# target_USB_interfaces_v3.net
KiCad netlist of a schematic drawn in Altium Designer
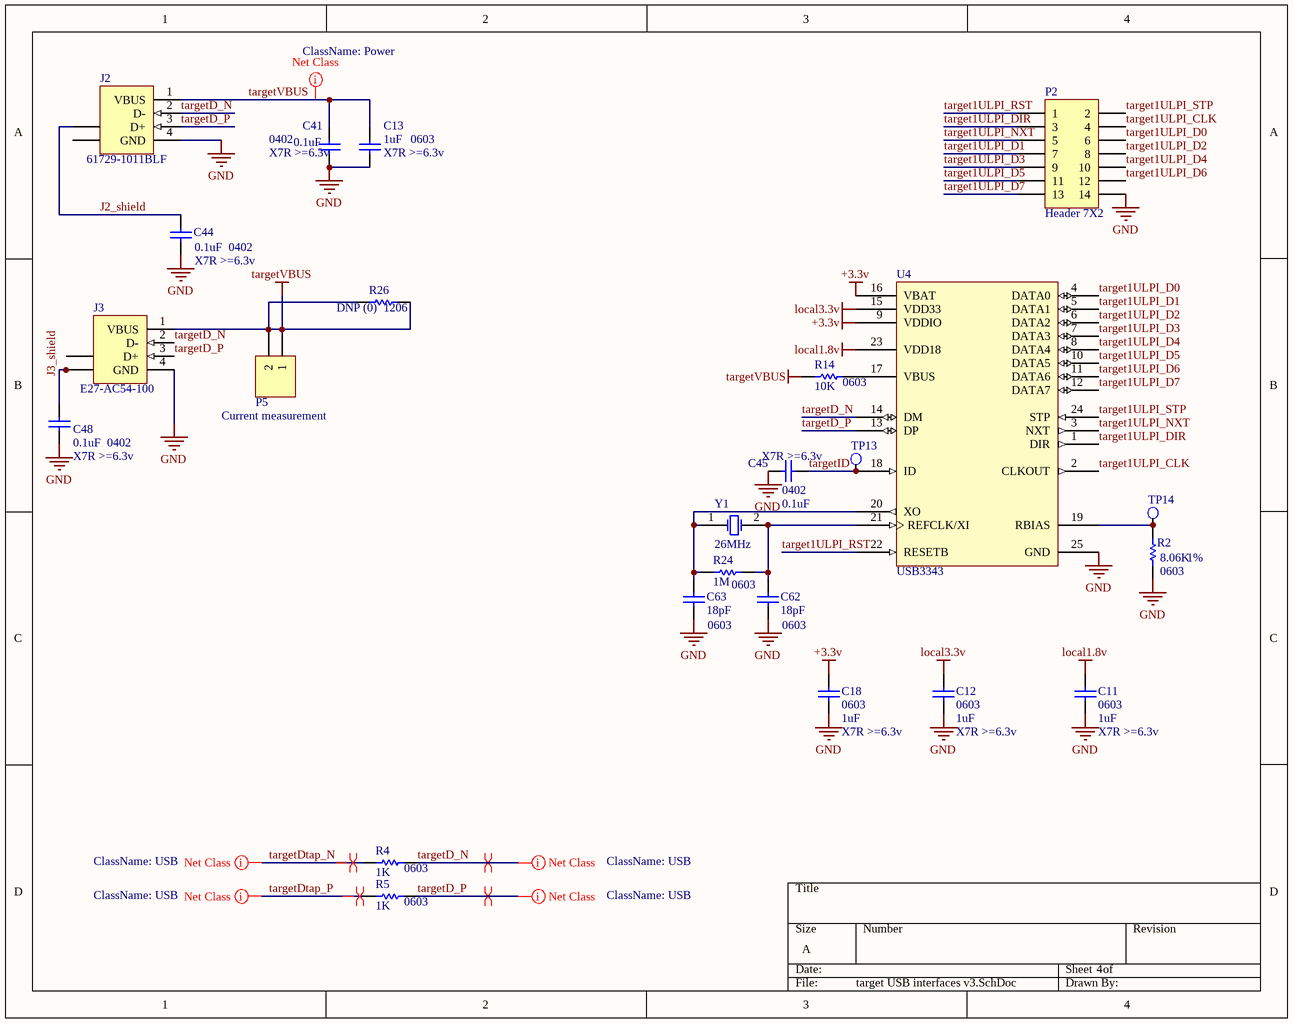
[diagram p0: target USB interfaces v3.SchDoc]

(export (version "E")
  (design (tool "Eeschema 10.0.6"))
  (components
    (comp (ref "C11")
      (value "1uF")
      (footprint "Chip_Capacitor_N:CAPC1608N")
      (description "CAP CER 10000PF 6.3V X5R 0201")
      (fields
        (field (name "PACKAGEREFERENCE") "0603")
        (field (name "RATING") "X7R >=6.3v")
        (field (name "TOLERANCE") "±10%")
      )
      (libsource (lib "Miscellaneous Devices") (part "Cap Semi"))
    )
    (comp (ref "C12")
      (value "1uF")
      (footprint "Chip_Capacitor_N:CAPC1608N")
      (description "CAP CER 10000PF 6.3V X5R 0201")
      (fields
        (field (name "PACKAGEREFERENCE") "0603")
        (field (name "RATING") "X7R >=6.3v")
        (field (name "TOLERANCE") "±10%")
      )
      (libsource (lib "Miscellaneous Devices") (part "Cap Semi"))
    )
    (comp (ref "C13")
      (value "1uF")
      (footprint "Chip_Capacitor_N:CAPC1608N")
      (description "Capacitor (Semiconductor SIM Model)")
      (fields
        (field (name "PACKAGEREFERENCE") "0603")
        (field (name "RATING") "X7R >=6.3v")
        (field (name "Comment") "Cap Semi")
      )
      (libsource (lib "Miscellaneous Devices") (part "Cap Semi"))
    )
    (comp (ref "C18")
      (value "1uF")
      (footprint "Chip_Capacitor_N:CAPC1608N")
      (description "CAP CER 10000PF 6.3V X5R 0201")
      (fields
        (field (name "PACKAGEREFERENCE") "0603")
        (field (name "RATING") "X7R >=6.3v")
        (field (name "TOLERANCE") "±10%")
      )
      (libsource (lib "Miscellaneous Devices") (part "Cap Semi"))
    )
    (comp (ref "C41")
      (value "0.1uF")
      (footprint "CAPC1005N")
      (description "Capacitor (Semiconductor SIM Model)")
      (fields
        (field (name "PACKAGEREFERENCE") "0402")
        (field (name "RATING") "X7R >=6.3v")
        (field (name "TOLERANCE") "±10%")
        (field (name "Comment") "Cap Semi")
      )
      (libsource (lib "Miscellaneous Devices") (part "Cap Semi"))
    )
    (comp (ref "C44")
      (value "0.1uF")
      (footprint "CAPC1005N")
      (description "Capacitor (Semiconductor SIM Model)")
      (fields
        (field (name "PACKAGEREFERENCE") "0402")
        (field (name "RATING") "X7R >=6.3v")
        (field (name "TOLERANCE") "±10%")
        (field (name "Comment") "Cap Semi")
      )
      (libsource (lib "Miscellaneous Devices") (part "Cap Semi"))
    )
    (comp (ref "C45")
      (value "0.1uF")
      (footprint "CAPC1005N")
      (description "Capacitor (Semiconductor SIM Model)")
      (fields
        (field (name "PACKAGEREFERENCE") "0402")
        (field (name "RATING") "X7R >=6.3v")
        (field (name "TOLERANCE") "±10%")
        (field (name "Comment") "Cap Semi")
      )
      (libsource (lib "Miscellaneous Devices") (part "Cap Semi"))
    )
    (comp (ref "C48")
      (value "0.1uF")
      (footprint "CAPC1005N")
      (description "Capacitor (Semiconductor SIM Model)")
      (fields
        (field (name "PACKAGEREFERENCE") "0402")
        (field (name "RATING") "X7R >=6.3v")
        (field (name "TOLERANCE") "±10%")
        (field (name "Comment") "Cap Semi")
      )
      (libsource (lib "Miscellaneous Devices") (part "Cap Semi"))
    )
    (comp (ref "C62")
      (value "18pF")
      (footprint "Chip_Capacitor_N:CAPC1608N")
      (description "Capacitor (Semiconductor SIM Model)")
      (fields (field (name "PACKAGEREFERENCE") "0603") (field (name "Comment") "Cap Semi"))
      (libsource (lib "Miscellaneous Devices") (part "Cap Semi"))
    )
    (comp (ref "C63")
      (value "18pF")
      (footprint "Chip_Capacitor_N:CAPC1608N")
      (description "Capacitor (Semiconductor SIM Model)")
      (fields (field (name "PACKAGEREFERENCE") "0603") (field (name "Comment") "Cap Semi"))
      (libsource (lib "Miscellaneous Devices") (part "Cap Semi"))
    )
    (comp (ref "J2")
      (value "61729-1011BLF")
      (footprint "1-1470156")
      (description "USB 1.1, Right Angle, Thru-Hole, B Type, Receptacle, 4 Position, White")
      (fields (field (name "Comment") "1-1470156-1"))
      (libsource (lib "AMP Serial Bus USB") (part "1-1470156-1"))
    )
    (comp (ref "J3")
      (value "E27-AC54-100")
      (footprint "787616")
      (description "USB 1.1, Right Angle, Thru-Hole, A Type, Receptacle, 4 Position, Black")
      (fields (field (name "Comment") "787616-1"))
      (libsource (lib "AMP Serial Bus USB") (part "787616-1"))
    )
    (comp (ref "P2")
      (value "Header 7X2")
      (footprint "HDR2X7")
      (description "Header, 7-Pin, Dual row")
      (libsource (lib "Miscellaneous Connectors") (part "Header 7X2"))
    )
    (comp (ref "P5")
      (value "Current measurement")
      (footprint "HDR1X2")
      (description "Header, 2-Pin")
      (libsource (lib "Miscellaneous Connectors") (part "Header 2"))
    )
    (comp (ref "R2")
      (value "8.06K")
      (footprint "RESC1608N")
      (description "Semiconductor Resistor")
      (fields
        (field (name "PACKAGEREFERENCE") "0603")
        (field (name "RATING") "1%")
        (field (name "Comment") "Res Semi")
      )
      (libsource (lib "Miscellaneous Devices") (part "Res Semi"))
    )
    (comp (ref "R4")
      (value "1K")
      (footprint "RESC1608N")
      (description "Semiconductor Resistor")
      (fields (field (name "PACKAGEREFERENCE") "0603") (field (name "Comment") "Res Semi"))
      (libsource (lib "Miscellaneous Devices") (part "Res Semi"))
    )
    (comp (ref "R5")
      (value "1K")
      (footprint "RESC1608N")
      (description "Semiconductor Resistor")
      (fields (field (name "PACKAGEREFERENCE") "0603") (field (name "Comment") "Res Semi"))
      (libsource (lib "Miscellaneous Devices") (part "Res Semi"))
    )
    (comp (ref "R14")
      (value "10K")
      (footprint "RESC1608N")
      (description "Semiconductor Resistor")
      (fields (field (name "PACKAGEREFERENCE") "0603") (field (name "Comment") "Res Semi"))
      (libsource (lib "Miscellaneous Devices") (part "Res Semi"))
    )
    (comp (ref "R24")
      (value "1M")
      (footprint "RESC1608N")
      (description "Semiconductor Resistor")
      (fields (field (name "PACKAGEREFERENCE") "0603") (field (name "Comment") "Res Semi"))
      (libsource (lib "Miscellaneous Devices") (part "Res Semi"))
    )
    (comp (ref "R26")
      (value "DNP (0)")
      (footprint "RESC3216N")
      (description "Semiconductor Resistor")
      (fields (field (name "PACKAGEREFERENCE") "1206") (field (name "Comment") "Res Semi"))
      (libsource (lib "Miscellaneous Devices") (part "Res Semi"))
    )
    (comp (ref "TP13")
      (value "Test Point")
      (footprint "testpoint")
      (libsource (lib "OpenVizsla symbols") (part "Test Pad"))
    )
    (comp (ref "TP14")
      (value "Test Point")
      (footprint "testpoint")
      (libsource (lib "OpenVizsla symbols") (part "Test Pad"))
    )
    (comp (ref "U4")
      (value "USB3343")
      (footprint "SMSC USB334x QFN24")
      (description "Hi-Speed USB Transceiver with 1.8V-3.3V ULPI Interface - MHz Reference Clock")
      (libsource (lib "OpenVizsla symbols") (part "USB3343"))
    )
    (comp (ref "Y1")
      (value "26MHz")
      (footprint "HC49/4H_SMX")
      (description "Crystal Oscillator")
      (libsource (lib "Miscellaneous Devices") (part "XTAL"))
    )
  )
  (nets
    (net (code "1") (name "+3.3v") (class "Default")
      (node (ref "C18") (pin "1") (pinfunction "1_1") (pintype "passive"))
      (node (ref "U4") (pin "16") (pinfunction "VBAT_16") (pintype "power_in"))
      (node (ref "U4") (pin "9") (pinfunction "VDDIO_9") (pintype "power_in"))
    )
    (net (code "2") (name "/J2_shield") (class "Default")
      (node (ref "C44") (pin "2") (pinfunction "2_2") (pintype "passive"))
      (node (ref "J2") (pin "5") (pinfunction "SHLD_5") (pintype "passive"))
    )
    (net (code "3") (name "/J3_shield") (class "Default")
      (node (ref "C48") (pin "2") (pinfunction "2_2") (pintype "passive"))
      (node (ref "J3") (pin "6") (pinfunction "SHLD_6") (pintype "passive"))
    )
    (net (code "4") (name "/target1ULPI_CLK") (class "Default")
      (node (ref "P2") (pin "4") (pinfunction "4_4") (pintype "passive"))
      (node (ref "U4") (pin "2") (pinfunction "CLKOUT_2") (pintype "output"))
    )
    (net (code "5") (name "/target1ULPI_D0") (class "Default")
      (node (ref "P2") (pin "6") (pinfunction "6_6") (pintype "passive"))
      (node (ref "U4") (pin "4") (pinfunction "DATA0_4") (pintype "bidirectional"))
    )
    (net (code "6") (name "/target1ULPI_D1") (class "Default")
      (node (ref "P2") (pin "7") (pinfunction "7_7") (pintype "passive"))
      (node (ref "U4") (pin "5") (pinfunction "DATA1_5") (pintype "bidirectional"))
    )
    (net (code "7") (name "/target1ULPI_D2") (class "Default")
      (node (ref "P2") (pin "8") (pinfunction "8_8") (pintype "passive"))
      (node (ref "U4") (pin "6") (pinfunction "DATA2_6") (pintype "bidirectional"))
    )
    (net (code "8") (name "/target1ULPI_D3") (class "Default")
      (node (ref "P2") (pin "9") (pinfunction "9_9") (pintype "passive"))
      (node (ref "U4") (pin "7") (pinfunction "DATA3_7") (pintype "bidirectional"))
    )
    (net (code "9") (name "/target1ULPI_D4") (class "Default")
      (node (ref "P2") (pin "10") (pinfunction "10_10") (pintype "passive"))
      (node (ref "U4") (pin "8") (pinfunction "DATA4_8") (pintype "bidirectional"))
    )
    (net (code "10") (name "/target1ULPI_D5") (class "Default")
      (node (ref "P2") (pin "11") (pinfunction "11_11") (pintype "passive"))
      (node (ref "U4") (pin "10") (pinfunction "DATA5_10") (pintype "bidirectional"))
    )
    (net (code "11") (name "/target1ULPI_D6") (class "Default")
      (node (ref "P2") (pin "12") (pinfunction "12_12") (pintype "passive"))
      (node (ref "U4") (pin "11") (pinfunction "DATA6_11") (pintype "bidirectional"))
    )
    (net (code "12") (name "/target1ULPI_D7") (class "Default")
      (node (ref "P2") (pin "13") (pinfunction "13_13") (pintype "passive"))
      (node (ref "U4") (pin "12") (pinfunction "DATA7_12") (pintype "bidirectional"))
    )
    (net (code "13") (name "/target1ULPI_DIR") (class "Default")
      (node (ref "P2") (pin "3") (pinfunction "3_3") (pintype "passive"))
      (node (ref "U4") (pin "1") (pinfunction "DIR_1") (pintype "output"))
    )
    (net (code "14") (name "/target1ULPI_NXT") (class "Default")
      (node (ref "P2") (pin "5") (pinfunction "5_5") (pintype "passive"))
      (node (ref "U4") (pin "3") (pinfunction "NXT_3") (pintype "output"))
    )
    (net (code "15") (name "/target1ULPI_RST") (class "Default")
      (node (ref "P2") (pin "1") (pinfunction "1_1") (pintype "passive"))
      (node (ref "U4") (pin "22") (pinfunction "RESETB_22") (pintype "input"))
    )
    (net (code "16") (name "/target1ULPI_STP") (class "Default")
      (node (ref "P2") (pin "2") (pinfunction "2_2") (pintype "passive"))
      (node (ref "U4") (pin "24") (pinfunction "STP_24") (pintype "input"))
    )
    (net (code "17") (name "/targetD_N") (class "Default")
      (node (ref "J2") (pin "2") (pinfunction "D-_2") (pintype "input"))
      (node (ref "J3") (pin "2") (pinfunction "D-_2") (pintype "input"))
      (node (ref "R4") (pin "1") (pinfunction "1_1") (pintype "passive"))
      (node (ref "U4") (pin "14") (pinfunction "DM_14") (pintype "bidirectional"))
    )
    (net (code "18") (name "/targetD_P") (class "Default")
      (node (ref "J2") (pin "3") (pinfunction "D+_3") (pintype "input"))
      (node (ref "J3") (pin "3") (pinfunction "D+_3") (pintype "input"))
      (node (ref "R5") (pin "1") (pinfunction "1_1") (pintype "passive"))
      (node (ref "U4") (pin "13") (pinfunction "DP_13") (pintype "bidirectional"))
    )
    (net (code "19") (name "/targetDtap_N") (class "Default")
      (node (ref "R4") (pin "2") (pinfunction "2_2") (pintype "passive"))
    )
    (net (code "20") (name "/targetDtap_P") (class "Default")
      (node (ref "R5") (pin "2") (pinfunction "2_2") (pintype "passive"))
    )
    (net (code "21") (name "/targetID") (class "Default")
      (node (ref "C45") (pin "1") (pinfunction "1_1") (pintype "passive"))
      (node (ref "TP13") (pin "1") (pinfunction "pin_1") (pintype "passive"))
      (node (ref "U4") (pin "18") (pinfunction "ID_18") (pintype "input"))
    )
    (net (code "22") (name "GND") (class "Default")
      (node (ref "C11") (pin "2") (pinfunction "2_2") (pintype "passive"))
      (node (ref "C12") (pin "2") (pinfunction "2_2") (pintype "passive"))
      (node (ref "C13") (pin "1") (pinfunction "1_1") (pintype "passive"))
      (node (ref "C18") (pin "2") (pinfunction "2_2") (pintype "passive"))
      (node (ref "C41") (pin "1") (pinfunction "1_1") (pintype "passive"))
      (node (ref "C44") (pin "1") (pinfunction "1_1") (pintype "passive"))
      (node (ref "C45") (pin "2") (pinfunction "2_2") (pintype "passive"))
      (node (ref "C48") (pin "1") (pinfunction "1_1") (pintype "passive"))
      (node (ref "C62") (pin "1") (pinfunction "1_1") (pintype "passive"))
      (node (ref "C63") (pin "1") (pinfunction "1_1") (pintype "passive"))
      (node (ref "J2") (pin "4") (pinfunction "GND_4") (pintype "power_in"))
      (node (ref "J3") (pin "4") (pinfunction "GND_4") (pintype "power_in"))
      (node (ref "P2") (pin "14") (pinfunction "14_14") (pintype "passive"))
      (node (ref "R2") (pin "1") (pinfunction "1_1") (pintype "passive"))
      (node (ref "U4") (pin "25") (pinfunction "GND_25") (pintype "power_in"))
    )
    (net (code "23") (name "Net-(TP14-pin)") (class "Default")
      (node (ref "R2") (pin "2") (pinfunction "2_2") (pintype "passive"))
      (node (ref "TP14") (pin "1") (pinfunction "pin_1") (pintype "passive"))
      (node (ref "U4") (pin "19") (pinfunction "RBIAS_19") (pintype "passive"))
    )
    (net (code "24") (name "Net-(U4-REFCLK{slash}XI)") (class "Default")
      (node (ref "C62") (pin "2") (pinfunction "2_2") (pintype "passive"))
      (node (ref "R24") (pin "1") (pinfunction "1_1") (pintype "passive"))
      (node (ref "U4") (pin "21") (pinfunction "REFCLK/XI_21") (pintype "input"))
      (node (ref "Y1") (pin "2") (pinfunction "OSC2_2") (pintype "passive"))
    )
    (net (code "25") (name "Net-(U4-VBUS)") (class "Default")
      (node (ref "R14") (pin "1") (pinfunction "1_1") (pintype "passive"))
      (node (ref "U4") (pin "17") (pinfunction "VBUS_17") (pintype "power_in"))
    )
    (net (code "26") (name "Net-(U4-XO)") (class "Default")
      (node (ref "C63") (pin "2") (pinfunction "2_2") (pintype "passive"))
      (node (ref "R24") (pin "2") (pinfunction "2_2") (pintype "passive"))
      (node (ref "U4") (pin "20") (pinfunction "XO_20") (pintype "output"))
      (node (ref "Y1") (pin "1") (pinfunction "OSC1_1") (pintype "passive"))
    )
    (net (code "27") (name "local1.8v") (class "Default")
      (node (ref "C11") (pin "1") (pinfunction "1_1") (pintype "passive"))
      (node (ref "U4") (pin "23") (pinfunction "VDD18_23") (pintype "power_in"))
    )
    (net (code "28") (name "local3.3v") (class "Default")
      (node (ref "C12") (pin "1") (pinfunction "1_1") (pintype "passive"))
      (node (ref "U4") (pin "15") (pinfunction "VDD33_15") (pintype "power_in"))
    )
    (net (code "29") (name "targetVBUS") (class "Default")
      (node (ref "C13") (pin "2") (pinfunction "2_2") (pintype "passive"))
      (node (ref "C41") (pin "2") (pinfunction "2_2") (pintype "passive"))
      (node (ref "J2") (pin "1") (pinfunction "VBUS_1") (pintype "power_in"))
      (node (ref "J3") (pin "1") (pinfunction "VBUS_1") (pintype "power_in"))
      (node (ref "P5") (pin "1") (pinfunction "1_1") (pintype "passive"))
      (node (ref "P5") (pin "2") (pinfunction "2_2") (pintype "passive"))
      (node (ref "R14") (pin "2") (pinfunction "2_2") (pintype "passive"))
      (node (ref "R26") (pin "1") (pinfunction "1_1") (pintype "passive"))
      (node (ref "R26") (pin "2") (pinfunction "2_2") (pintype "passive"))
    )
    (net (code "30") (name "unconnected-(J2-SHLD-Pad6)") (class "Default")
      (node (ref "J2") (pin "6") (pinfunction "SHLD_6") (pintype "passive"))
    )
    (net (code "31") (name "unconnected-(J3-SHLD-Pad5)") (class "Default")
      (node (ref "J3") (pin "5") (pinfunction "SHLD_5") (pintype "passive"))
    )
  )
)
